# DS1339B_RTC_breakout.net
KiCad netlist of a schematic drawn in EAGLE
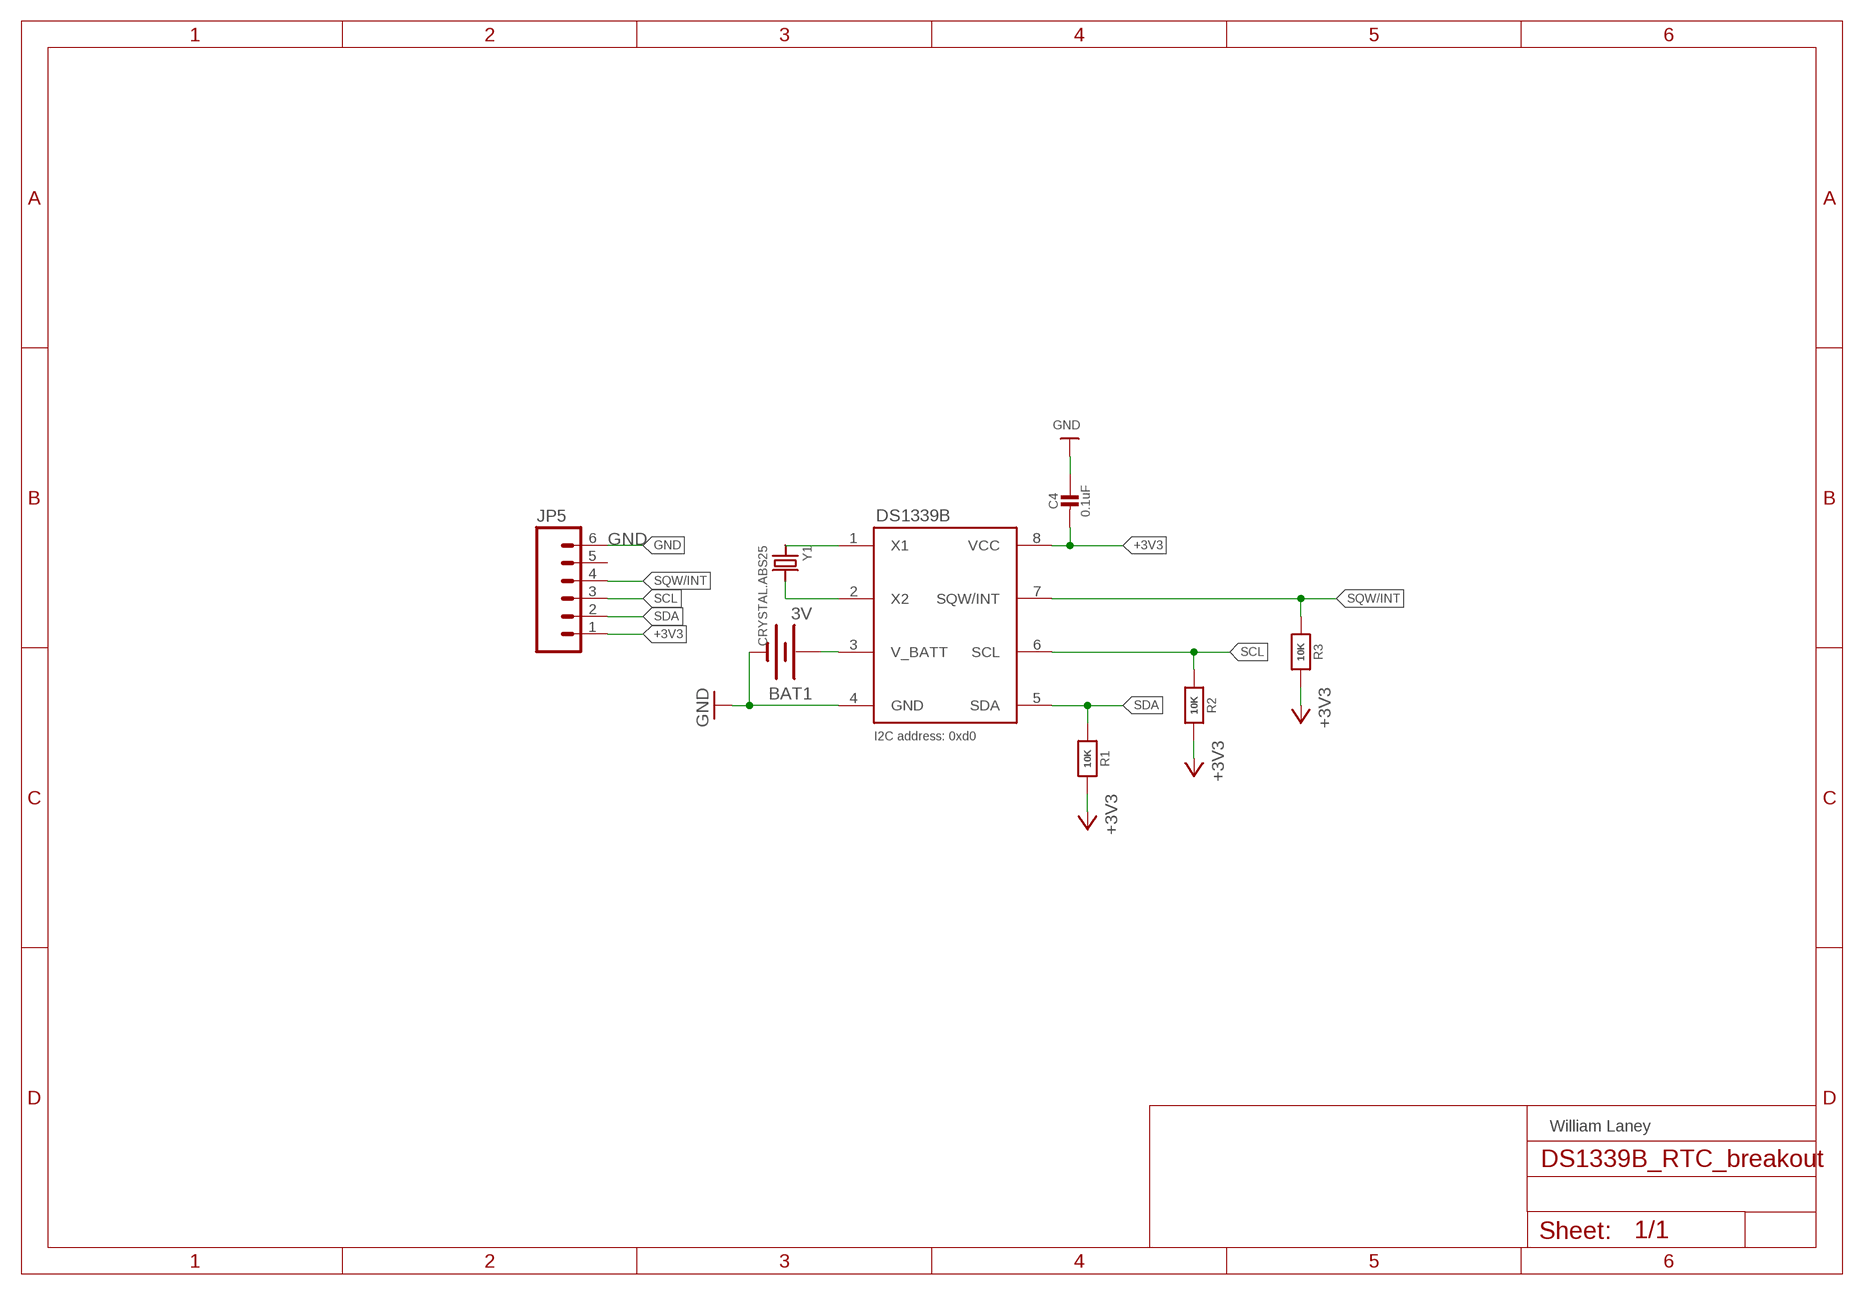
[diagram p0: schematic, sheet 1]

(export (version "E")
  (design (tool "Eeschema 10.0.6"))
  (components
    (comp (ref "BAT1")
      (value "3V")
      (footprint "eagle-import:BATTCON_12MM_CURVED")
      (libsource (lib "eagle-import") (part "BATTERY"))
    )
    (comp (ref "C4")
      (value "0.1uF")
      (footprint "eagle-import:0805-NO")
      (libsource (lib "eagle-import") (part "CAP_CERAMIC0805-NOOUTLINE"))
    )
    (comp (ref "JP5")
      (value "M06SIP")
      (footprint "eagle-import:1X06")
      (libsource (lib "eagle-import") (part "M06SIP"))
    )
    (comp (ref "R1")
      (value "10K")
      (footprint "eagle-import:0805-NO")
      (libsource (lib "eagle-import") (part "RESISTOR0805_NOOUTLINE"))
    )
    (comp (ref "R2")
      (value "10K")
      (footprint "eagle-import:0805-NO")
      (libsource (lib "eagle-import") (part "RESISTOR0805_NOOUTLINE"))
    )
    (comp (ref "R3")
      (value "10K")
      (footprint "eagle-import:0805-NO")
      (libsource (lib "eagle-import") (part "RESISTOR0805_NOOUTLINE"))
    )
    (comp (ref "U$1")
      (value "DS1339BDS1339B")
      (footprint "eagle-import:8U-SOP")
      (libsource (lib "eagle-import") (part "DS1339BDS1339B"))
    )
    (comp (ref "Y1")
      (value "CRYSTAL.ABS25")
      (footprint "eagle-import:ABS25")
      (libsource (lib "eagle-import") (part "CRYSTAL.ABS25"))
    )
  )
  (nets
    (net (code "1") (name "+3V3") (class "Default")
      (node (ref "C4") (pin "2") (pinfunction "2_2") (pintype "passive"))
      (node (ref "JP5") (pin "1") (pinfunction "1_1") (pintype "passive"))
      (node (ref "R1") (pin "2") (pinfunction "2_2") (pintype "passive"))
      (node (ref "R2") (pin "2") (pinfunction "2_2") (pintype "passive"))
      (node (ref "R3") (pin "2") (pinfunction "2_2") (pintype "passive"))
      (node (ref "U$1") (pin "8") (pinfunction "VCC_8") (pintype "bidirectional"))
    )
    (net (code "2") (name "GND") (class "Default")
      (node (ref "BAT1") (pin "GND") (pinfunction "-_GND") (pintype "power_in"))
      (node (ref "C4") (pin "1") (pinfunction "1_1") (pintype "passive"))
      (node (ref "JP5") (pin "6") (pinfunction "6_6") (pintype "passive"))
      (node (ref "U$1") (pin "4") (pinfunction "GND_4") (pintype "bidirectional"))
    )
    (net (code "3") (name "Net-(BAT1-+)") (class "Default")
      (node (ref "BAT1") (pin "PWR@1") (pinfunction "+_PWR@1") (pintype "power_in"))
      (node (ref "U$1") (pin "3") (pinfunction "V_BATT_3") (pintype "bidirectional"))
    )
    (net (code "4") (name "Net-(U$1-X1)") (class "Default")
      (node (ref "U$1") (pin "1") (pinfunction "X1_1") (pintype "bidirectional"))
      (node (ref "Y1") (pin "1") (pinfunction "1_1") (pintype "passive"))
    )
    (net (code "5") (name "Net-(U$1-X2)") (class "Default")
      (node (ref "U$1") (pin "2") (pinfunction "X2_2") (pintype "bidirectional"))
      (node (ref "Y1") (pin "4") (pinfunction "2_4") (pintype "passive"))
    )
    (net (code "6") (name "SCL") (class "Default")
      (node (ref "JP5") (pin "3") (pinfunction "3_3") (pintype "passive"))
      (node (ref "R2") (pin "1") (pinfunction "1_1") (pintype "passive"))
      (node (ref "U$1") (pin "6") (pinfunction "SCL_6") (pintype "bidirectional"))
    )
    (net (code "7") (name "SDA") (class "Default")
      (node (ref "JP5") (pin "2") (pinfunction "2_2") (pintype "passive"))
      (node (ref "R1") (pin "1") (pinfunction "1_1") (pintype "passive"))
      (node (ref "U$1") (pin "5") (pinfunction "SDA_5") (pintype "bidirectional"))
    )
    (net (code "8") (name "SQW{slash}INT") (class "Default")
      (node (ref "JP5") (pin "4") (pinfunction "4_4") (pintype "passive"))
      (node (ref "R3") (pin "1") (pinfunction "1_1") (pintype "passive"))
      (node (ref "U$1") (pin "7") (pinfunction "SQW/INT_7") (pintype "bidirectional"))
    )
    (net (code "9") (name "unconnected-(JP5-Pad5)") (class "Default")
      (node (ref "JP5") (pin "5") (pinfunction "5_5") (pintype "passive"))
    )
  )
)
